# ATmega128RFA1-DevBoard.net
KiCad netlist of a schematic drawn in EAGLE
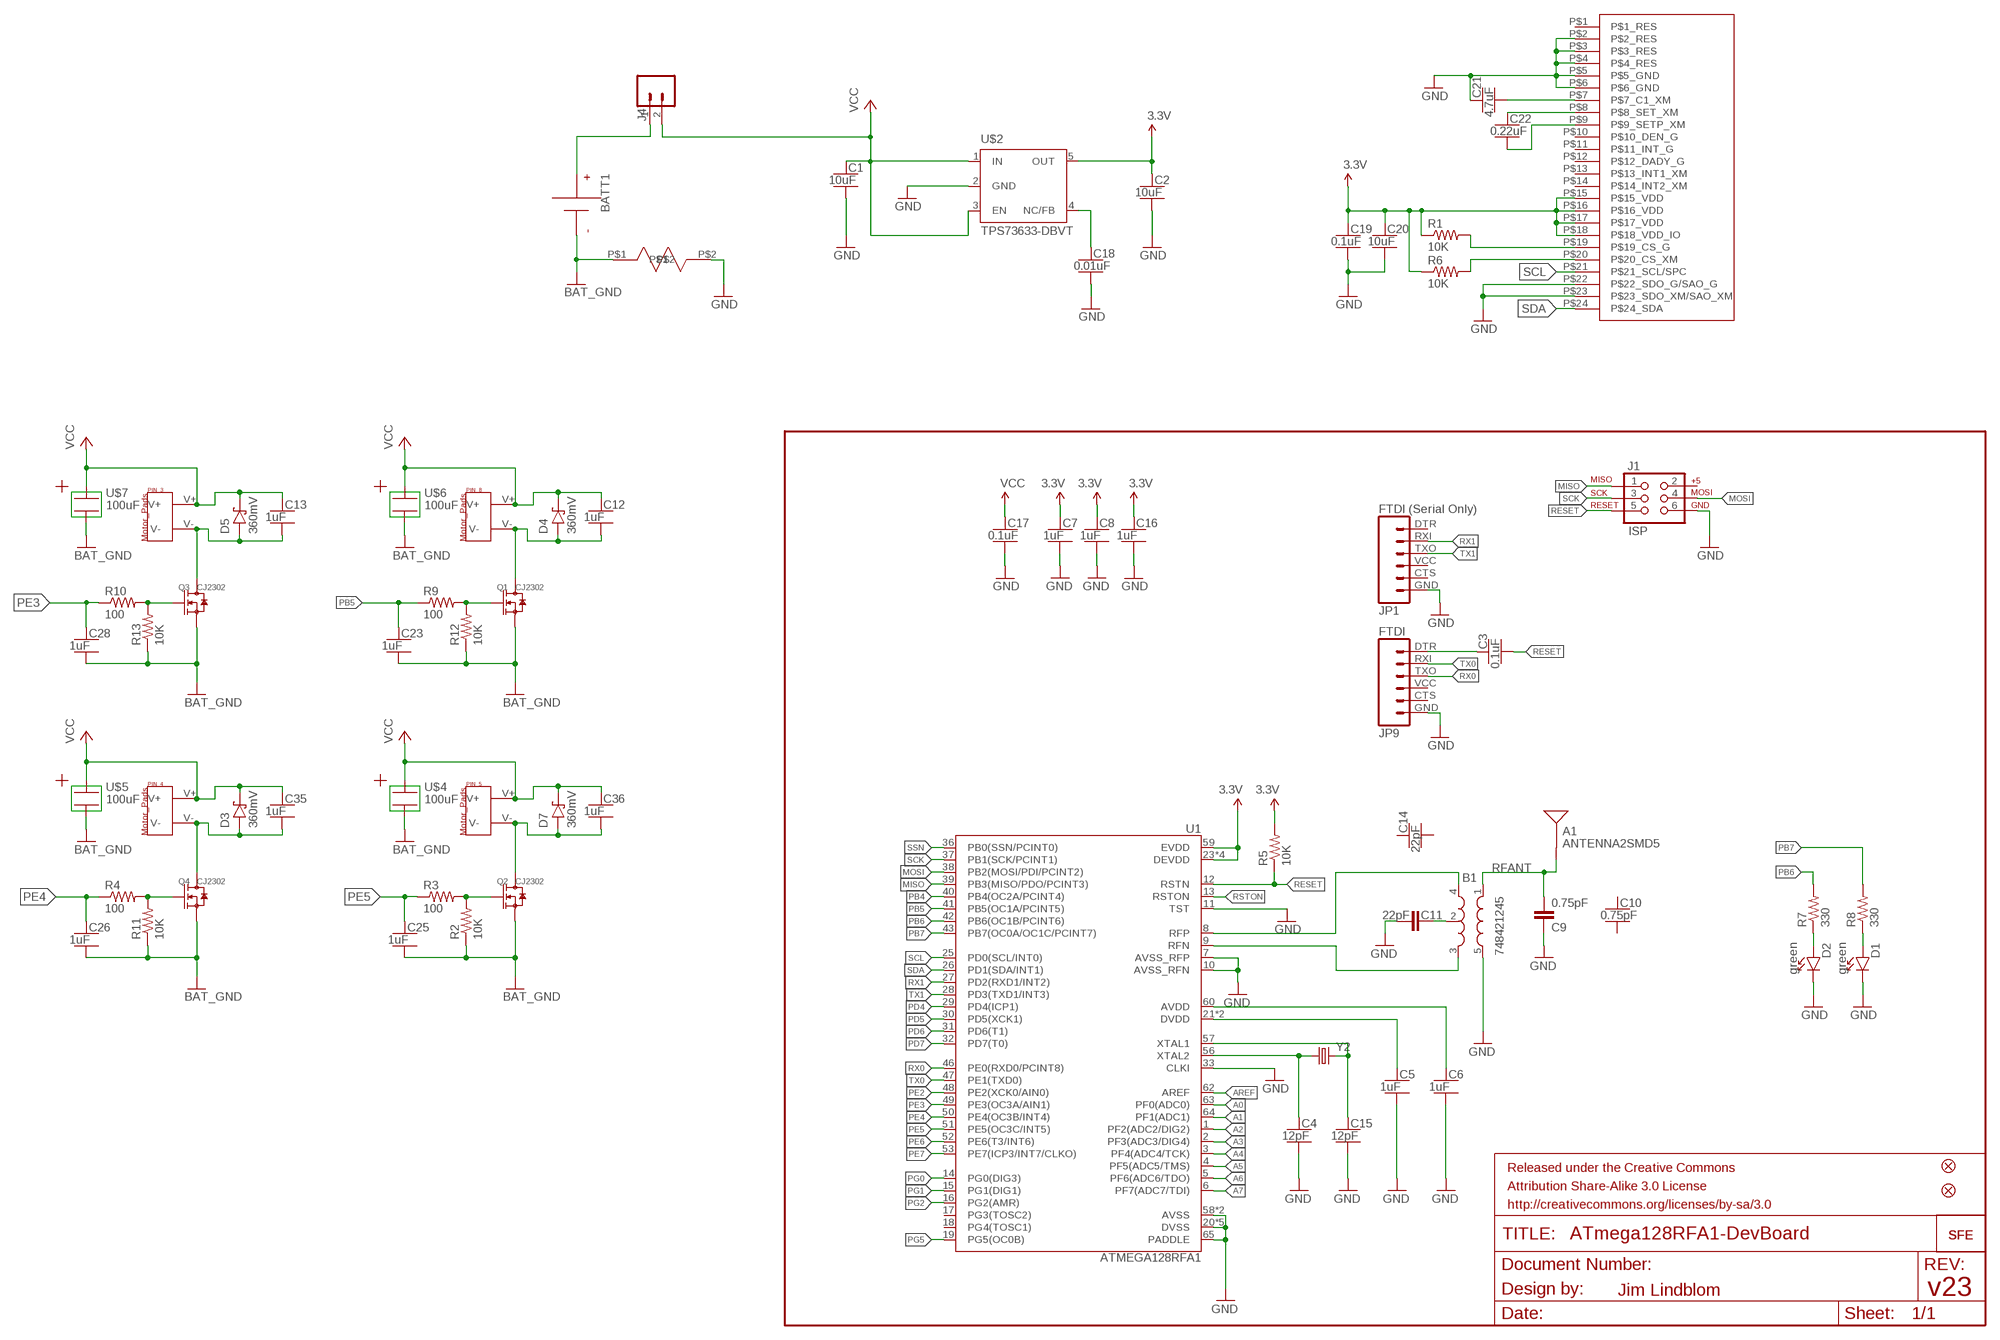
[diagram p0: schematic, sheet 1]

(export (version "E")
  (design (tool "Eeschema 10.0.6"))
  (components
    (comp (ref "A1")
      (value "ANTENNA2SMD5")
      (footprint "eagle-import:ANTENNA-CHIP5")
      (libsource (lib "eagle-import") (part "ANTENNA2SMD5"))
    )
    (comp (ref "B1")
      (value "748421245")
      (footprint "eagle-import:BALUN")
      (libsource (lib "eagle-import") (part "BALUN0805"))
    )
    (comp (ref "BATT1")
      (value "BATTERY-HUBSAN-W/HOLDER")
      (footprint "eagle-import:BATTERY-W_HOLDER-380MAH-HUBSAN")
      (libsource (lib "eagle-import") (part "BATTERY-HUBSAN-W/HOLDER"))
    )
    (comp (ref "C1")
      (value "10uF")
      (footprint "eagle-import:CAPC2012X140_HS")
      (fields
        (field (name "MFR") "Murata Electronics North America")
        (field (name "MPN") "GRM21BR61E106KA73L")
      )
      (libsource (lib "eagle-import") (part "CAPACITOR-NP_SMD-2012-0805_CERAMIC-10UF"))
    )
    (comp (ref "C2")
      (value "10uF")
      (footprint "eagle-import:CAPC2012X140_HS")
      (fields
        (field (name "MFR") "Murata Electronics North America")
        (field (name "MPN") "GRM21BR61E106KA73L")
      )
      (libsource (lib "eagle-import") (part "CAPACITOR-NP_SMD-2012-0805_CERAMIC-10UF"))
    )
    (comp (ref "C3")
      (value "0.1uF")
      (footprint "eagle-import:CAPC2012X140_HS")
      (fields
        (field (name "MFR") "Murata Electronics North America")
        (field (name "MPN") "GRM21BR71H104KA01L")
      )
      (libsource (lib "eagle-import") (part "CAPACITOR-NP_SMD-2012-0805_CERAMIC-0.1UF"))
    )
    (comp (ref "C4")
      (value "12pF")
      (footprint "eagle-import:CAPC2012X140_HS")
      (fields
        (field (name "MFR") "Murata Electronics North America")
        (field (name "MPN") "GRM21A5C2E120JW01D")
      )
      (libsource (lib "eagle-import") (part "CAPACITOR-NP_SMD-2012-0805_CERAMIC-12PF"))
    )
    (comp (ref "C5")
      (value "1uF")
      (footprint "eagle-import:CAPC2012X140_HS")
      (fields
        (field (name "MFR") "Murata Electronics North America")
        (field (name "MPN") "GRM21BR71H105KA12L")
      )
      (libsource (lib "eagle-import") (part "CAPACITOR-NP_SMD-2012-0805_CERAMIC-1UF"))
    )
    (comp (ref "C6")
      (value "1uF")
      (footprint "eagle-import:CAPC2012X140_HS")
      (fields
        (field (name "MFR") "Murata Electronics North America")
        (field (name "MPN") "GRM21BR71H105KA12L")
      )
      (libsource (lib "eagle-import") (part "CAPACITOR-NP_SMD-2012-0805_CERAMIC-1UF"))
    )
    (comp (ref "C7")
      (value "1uF")
      (footprint "eagle-import:CAPC2012X140_HS")
      (fields
        (field (name "MFR") "Murata Electronics North America")
        (field (name "MPN") "GRM21BR71H105KA12L")
      )
      (libsource (lib "eagle-import") (part "CAPACITOR-NP_SMD-2012-0805_CERAMIC-1UF"))
    )
    (comp (ref "C8")
      (value "1uF")
      (footprint "eagle-import:CAPC2012X140_HS")
      (fields
        (field (name "MFR") "Murata Electronics North America")
        (field (name "MPN") "GRM21BR71H105KA12L")
      )
      (libsource (lib "eagle-import") (part "CAPACITOR-NP_SMD-2012-0805_CERAMIC-1UF"))
    )
    (comp (ref "C9")
      (value "0.75pF")
      (footprint "eagle-import:0402-CAP")
      (libsource (lib "eagle-import") (part "CAP0402-CAP"))
    )
    (comp (ref "C10")
      (value "0.75pF")
      (footprint "eagle-import:CAPC2012X140_HS")
      (fields
        (field (name "MFR") "Murata Electronics North America")
        (field (name "MPN") "GQM2195C2AR75CB01D")
      )
      (libsource (lib "eagle-import") (part "CAPACITOR-NP_SMD-2012-0805_CERAMIC-0.75PF"))
    )
    (comp (ref "C11")
      (value "22pF")
      (footprint "eagle-import:0402-CAP")
      (libsource (lib "eagle-import") (part "CAP0402-CAP"))
    )
    (comp (ref "C12")
      (value "1uF")
      (footprint "eagle-import:CAPC2012X140_HS")
      (fields
        (field (name "MFR") "Murata Electronics North America")
        (field (name "MPN") "GRM21BR71H105KA12L")
      )
      (libsource (lib "eagle-import") (part "CAPACITOR-NP_SMD-2012-0805_CERAMIC-1UF"))
    )
    (comp (ref "C13")
      (value "1uF")
      (footprint "eagle-import:CAPC2012X140_HS")
      (fields
        (field (name "MFR") "Murata Electronics North America")
        (field (name "MPN") "GRM21BR71H105KA12L")
      )
      (libsource (lib "eagle-import") (part "CAPACITOR-NP_SMD-2012-0805_CERAMIC-1UF"))
    )
    (comp (ref "C14")
      (value "22pF")
      (footprint "eagle-import:CAPC2012X140_HS")
      (fields
        (field (name "MFR") "Murata Electronics North America")
        (field (name "MPN") "GRM21A5C2E220JW01D")
      )
      (libsource (lib "eagle-import") (part "CAPACITOR-NP_SMD-2012-0805_CERAMIC-22PF"))
    )
    (comp (ref "C15")
      (value "12pF")
      (footprint "eagle-import:CAPC2012X140_HS")
      (fields
        (field (name "MFR") "Murata Electronics North America")
        (field (name "MPN") "GRM21A5C2E120JW01D")
      )
      (libsource (lib "eagle-import") (part "CAPACITOR-NP_SMD-2012-0805_CERAMIC-12PF"))
    )
    (comp (ref "C16")
      (value "1uF")
      (footprint "eagle-import:CAPC2012X140_HS")
      (fields
        (field (name "MFR") "Murata Electronics North America")
        (field (name "MPN") "GRM21BR71H105KA12L")
      )
      (libsource (lib "eagle-import") (part "CAPACITOR-NP_SMD-2012-0805_CERAMIC-1UF"))
    )
    (comp (ref "C17")
      (value "0.1uF")
      (footprint "eagle-import:CAPC2012X140_HS")
      (fields
        (field (name "MFR") "Murata Electronics North America")
        (field (name "MPN") "GRM21BR71H104KA01L")
      )
      (libsource (lib "eagle-import") (part "CAPACITOR-NP_SMD-2012-0805_CERAMIC-0.1UF"))
    )
    (comp (ref "C18")
      (value "0.01uF")
      (footprint "eagle-import:CAPC2012X140_HS")
      (fields
        (field (name "MFR") "Murata Electronics North America")
        (field (name "MPN") "GRM2195C1H103FA01D")
      )
      (libsource (lib "eagle-import") (part "CAPACITOR-NP_SMD-2012-0805_CERAMIC-0.01UF"))
    )
    (comp (ref "C19")
      (value "0.1uF")
      (footprint "eagle-import:CAPC2012X140_HS")
      (fields
        (field (name "MFR") "Murata Electronics North America")
        (field (name "MPN") "GRM21BR71H104KA01L")
      )
      (libsource (lib "eagle-import") (part "CAPACITOR-NP_SMD-2012-0805_CERAMIC-0.1UF"))
    )
    (comp (ref "C20")
      (value "10uF")
      (footprint "eagle-import:CAPC2012X140_HS")
      (fields
        (field (name "MFR") "Murata Electronics North America")
        (field (name "MPN") "GRM21BR61E106KA73L")
      )
      (libsource (lib "eagle-import") (part "CAPACITOR-NP_SMD-2012-0805_CERAMIC-10UF"))
    )
    (comp (ref "C21")
      (value "4.7uF")
      (footprint "eagle-import:CAPC2012X140_HS")
      (fields
        (field (name "MFR") "Murata Electronics North America")
        (field (name "MPN") "GRM21BR61E475KA12L")
      )
      (libsource (lib "eagle-import") (part "CAPACITOR-NP_SMD-2012-0805_CERAMIC-4.7UF"))
    )
    (comp (ref "C22")
      (value "0.22uF")
      (footprint "eagle-import:CAPC2012X140_HS")
      (fields
        (field (name "MFR") "Murata Electronics North America")
        (field (name "MPN") "GRM21BR71H224KA01L")
      )
      (libsource (lib "eagle-import") (part "CAPACITOR-NP_SMD-2012-0805_CERAMIC-0.22UF"))
    )
    (comp (ref "C23")
      (value "1uF")
      (footprint "eagle-import:CAPC2012X140_HS")
      (fields
        (field (name "MFR") "Murata Electronics North America")
        (field (name "MPN") "GRM21BR71H105KA12L")
      )
      (libsource (lib "eagle-import") (part "CAPACITOR-NP_SMD-2012-0805_CERAMIC-1UF"))
    )
    (comp (ref "C25")
      (value "1uF")
      (footprint "eagle-import:CAPC2012X140_HS")
      (fields
        (field (name "MFR") "Murata Electronics North America")
        (field (name "MPN") "GRM21BR71H105KA12L")
      )
      (libsource (lib "eagle-import") (part "CAPACITOR-NP_SMD-2012-0805_CERAMIC-1UF"))
    )
    (comp (ref "C26")
      (value "1uF")
      (footprint "eagle-import:CAPC2012X140_HS")
      (fields
        (field (name "MFR") "Murata Electronics North America")
        (field (name "MPN") "GRM21BR71H105KA12L")
      )
      (libsource (lib "eagle-import") (part "CAPACITOR-NP_SMD-2012-0805_CERAMIC-1UF"))
    )
    (comp (ref "C28")
      (value "1uF")
      (footprint "eagle-import:CAPC2012X140_HS")
      (fields
        (field (name "MFR") "Murata Electronics North America")
        (field (name "MPN") "GRM21BR71H105KA12L")
      )
      (libsource (lib "eagle-import") (part "CAPACITOR-NP_SMD-2012-0805_CERAMIC-1UF"))
    )
    (comp (ref "C35")
      (value "1uF")
      (footprint "eagle-import:CAPC2012X140_HS")
      (fields
        (field (name "MFR") "Murata Electronics North America")
        (field (name "MPN") "GRM21BR71H105KA12L")
      )
      (libsource (lib "eagle-import") (part "CAPACITOR-NP_SMD-2012-0805_CERAMIC-1UF"))
    )
    (comp (ref "C36")
      (value "1uF")
      (footprint "eagle-import:CAPC2012X140_HS")
      (fields
        (field (name "MFR") "Murata Electronics North America")
        (field (name "MPN") "GRM21BR71H105KA12L")
      )
      (libsource (lib "eagle-import") (part "CAPACITOR-NP_SMD-2012-0805_CERAMIC-1UF"))
    )
    (comp (ref "D1")
      (value "green")
      (footprint "eagle-import:LEDSC125X200X120-2_HS")
      (fields (field (name "MFR") "Lite-On Inc") (field (name "MPN") "LTST-C170GKT"))
      (libsource (lib "eagle-import") (part "DIODE-LED_SMD-2012-0805-GREEN"))
    )
    (comp (ref "D2")
      (value "green")
      (footprint "eagle-import:LEDSC125X200X120-2_HS")
      (fields (field (name "MFR") "Lite-On Inc") (field (name "MPN") "LTST-C170GKT"))
      (libsource (lib "eagle-import") (part "DIODE-LED_SMD-2012-0805-GREEN"))
    )
    (comp (ref "D3")
      (value "360mV")
      (footprint "eagle-import:SOD3716X135_HS")
      (fields
        (field (name "MFR") "Toshiba Semiconductor and Storage")
        (field (name "MPN") "CRS08(TE85L,Q,M)")
      )
      (libsource (lib "eagle-import") (part "DIODE-SCHOTTKY_SMD-SOD123-360MV"))
    )
    (comp (ref "D4")
      (value "360mV")
      (footprint "eagle-import:SOD3716X135_HS")
      (fields
        (field (name "MFR") "Toshiba Semiconductor and Storage")
        (field (name "MPN") "CRS08(TE85L,Q,M)")
      )
      (libsource (lib "eagle-import") (part "DIODE-SCHOTTKY_SMD-SOD123-360MV"))
    )
    (comp (ref "D5")
      (value "360mV")
      (footprint "eagle-import:SOD3716X135_HS")
      (fields
        (field (name "MFR") "Toshiba Semiconductor and Storage")
        (field (name "MPN") "CRS08(TE85L,Q,M)")
      )
      (libsource (lib "eagle-import") (part "DIODE-SCHOTTKY_SMD-SOD123-360MV"))
    )
    (comp (ref "D7")
      (value "360mV")
      (footprint "eagle-import:SOD3716X135_HS")
      (fields
        (field (name "MFR") "Toshiba Semiconductor and Storage")
        (field (name "MPN") "CRS08(TE85L,Q,M)")
      )
      (libsource (lib "eagle-import") (part "DIODE-SCHOTTKY_SMD-SOD123-360MV"))
    )
    (comp (ref "FID1")
      (value "FIDUCIALUFIDUCIAL")
      (footprint "eagle-import:MICRO-FIDUCIAL")
      (libsource (lib "eagle-import") (part "FIDUCIALUFIDUCIAL"))
    )
    (comp (ref "FID2")
      (value "FIDUCIALUFIDUCIAL")
      (footprint "eagle-import:MICRO-FIDUCIAL")
      (libsource (lib "eagle-import") (part "FIDUCIALUFIDUCIAL"))
    )
    (comp (ref "J1")
      (value "ISP")
      (footprint "eagle-import:2X3-NS")
      (libsource (lib "eagle-import") (part "AVR_SPI_PRG_6NS"))
    )
    (comp (ref "J4")
      (value "MALE_HEADER_2POS-2X1-0.1IN")
      (footprint "eagle-import:MALE_HEADER_2X1_0.1IN")
      (fields
        (field (name "MFR") "3M")
        (field (name "MPN") "961102-6404-AR")
        (field (name "CREATOR") "SWANSON")
      )
      (libsource (lib "eagle-import") (part "MALE_HEADER_2POS-2X1-0.1IN"))
    )
    (comp (ref "JP1")
      (value "FTDI (Serial Only)")
      (footprint "eagle-import:FTDI_BASIC")
      (libsource (lib "eagle-import") (part "FTDI_BASICPTH"))
    )
    (comp (ref "JP4")
      (value "LOGO-SFENEW")
      (footprint "eagle-import:SFE-NEW-WEBLOGO")
      (libsource (lib "eagle-import") (part "LOGO-SFENEW"))
    )
    (comp (ref "JP9")
      (value "FTDI")
      (footprint "eagle-import:FTDI_BASIC")
      (libsource (lib "eagle-import") (part "FTDI_BASICPTH"))
    )
    (comp (ref "JP10")
      (value "LOGO-SFENEW")
      (footprint "eagle-import:SFE-NEW-WEBLOGO")
      (libsource (lib "eagle-import") (part "LOGO-SFENEW"))
    )
    (comp (ref "PIN_3")
      (value "MOTOR_PADS")
      (footprint "eagle-import:MOTOR_PADS")
      (libsource (lib "eagle-import") (part "MOTOR_PADS"))
    )
    (comp (ref "PIN_4")
      (value "MOTOR_PADS")
      (footprint "eagle-import:MOTOR_PADS")
      (libsource (lib "eagle-import") (part "MOTOR_PADS"))
    )
    (comp (ref "PIN_5")
      (value "MOTOR_PADS")
      (footprint "eagle-import:MOTOR_PADS")
      (libsource (lib "eagle-import") (part "MOTOR_PADS"))
    )
    (comp (ref "PIN_8")
      (value "MOTOR_PADS")
      (footprint "eagle-import:MOTOR_PADS")
      (libsource (lib "eagle-import") (part "MOTOR_PADS"))
    )
    (comp (ref "Q1")
      (value "CJ2302")
      (footprint "eagle-import:SOT-23")
      (libsource (lib "eagle-import") (part "SMD-MOSFET-N-CH-20V-2.1A-CJ2302(SOT-23)"))
    )
    (comp (ref "Q2")
      (value "CJ2302")
      (footprint "eagle-import:SOT-23")
      (libsource (lib "eagle-import") (part "SMD-MOSFET-N-CH-20V-2.1A-CJ2302(SOT-23)"))
    )
    (comp (ref "Q3")
      (value "CJ2302")
      (footprint "eagle-import:SOT-23")
      (libsource (lib "eagle-import") (part "SMD-MOSFET-N-CH-20V-2.1A-CJ2302(SOT-23)"))
    )
    (comp (ref "Q4")
      (value "CJ2302")
      (footprint "eagle-import:SOT-23")
      (libsource (lib "eagle-import") (part "SMD-MOSFET-N-CH-20V-2.1A-CJ2302(SOT-23)"))
    )
    (comp (ref "R1")
      (value "10K")
      (footprint "eagle-import:RESC2012X60_HS")
      (fields (field (name "MFR") "Yageo") (field (name "MPN") "RC0805JR-0710KL"))
      (libsource (lib "eagle-import") (part "RESISTOR_SMD-2012-0805-10K"))
    )
    (comp (ref "R2")
      (value "10K")
      (footprint "eagle-import:RESC2012X60_HS")
      (fields (field (name "MFR") "Yageo") (field (name "MPN") "RC0805JR-0710KL"))
      (libsource (lib "eagle-import") (part "RESISTOR_SMD-2012-0805-10K"))
    )
    (comp (ref "R3")
      (value "100")
      (footprint "eagle-import:RESC2012X60_HS")
      (fields (field (name "MFR") "Yageo") (field (name "MPN") "RC0805JR-07100RL"))
      (libsource (lib "eagle-import") (part "RESISTOR_SMD-2012-0805-100"))
    )
    (comp (ref "R4")
      (value "100")
      (footprint "eagle-import:RESC2012X60_HS")
      (fields (field (name "MFR") "Yageo") (field (name "MPN") "RC0805JR-07100RL"))
      (libsource (lib "eagle-import") (part "RESISTOR_SMD-2012-0805-100"))
    )
    (comp (ref "R5")
      (value "10K")
      (footprint "eagle-import:RESC2012X60_HS")
      (fields (field (name "MFR") "Yageo") (field (name "MPN") "RC0805JR-0710KL"))
      (libsource (lib "eagle-import") (part "RESISTOR_SMD-2012-0805-10K"))
    )
    (comp (ref "R6")
      (value "10K")
      (footprint "eagle-import:RESC2012X60_HS")
      (fields (field (name "MFR") "Yageo") (field (name "MPN") "RC0805JR-0710KL"))
      (libsource (lib "eagle-import") (part "RESISTOR_SMD-2012-0805-10K"))
    )
    (comp (ref "R7")
      (value "330")
      (footprint "eagle-import:RESC2012X60_HS")
      (fields (field (name "MFR") "Yageo") (field (name "MPN") "RC0805JR-07330RL"))
      (libsource (lib "eagle-import") (part "RESISTOR_SMD-2012-0805-330"))
    )
    (comp (ref "R8")
      (value "330")
      (footprint "eagle-import:RESC2012X60_HS")
      (fields (field (name "MFR") "Yageo") (field (name "MPN") "RC0805JR-07330RL"))
      (libsource (lib "eagle-import") (part "RESISTOR_SMD-2012-0805-330"))
    )
    (comp (ref "R9")
      (value "100")
      (footprint "eagle-import:RESC2012X60_HS")
      (fields (field (name "MFR") "Yageo") (field (name "MPN") "RC0805JR-07100RL"))
      (libsource (lib "eagle-import") (part "RESISTOR_SMD-2012-0805-100"))
    )
    (comp (ref "R10")
      (value "100")
      (footprint "eagle-import:RESC2012X60_HS")
      (fields (field (name "MFR") "Yageo") (field (name "MPN") "RC0805JR-07100RL"))
      (libsource (lib "eagle-import") (part "RESISTOR_SMD-2012-0805-100"))
    )
    (comp (ref "R11")
      (value "10K")
      (footprint "eagle-import:RESC2012X60_HS")
      (fields (field (name "MFR") "Yageo") (field (name "MPN") "RC0805JR-0710KL"))
      (libsource (lib "eagle-import") (part "RESISTOR_SMD-2012-0805-10K"))
    )
    (comp (ref "R12")
      (value "10K")
      (footprint "eagle-import:RESC2012X60_HS")
      (fields (field (name "MFR") "Yageo") (field (name "MPN") "RC0805JR-0710KL"))
      (libsource (lib "eagle-import") (part "RESISTOR_SMD-2012-0805-10K"))
    )
    (comp (ref "R13")
      (value "10K")
      (footprint "eagle-import:RESC2012X60_HS")
      (fields (field (name "MFR") "Yageo") (field (name "MPN") "RC0805JR-0710KL"))
      (libsource (lib "eagle-import") (part "RESISTOR_SMD-2012-0805-10K"))
    )
    (comp (ref "U$1")
      (value "IMU")
      (footprint "eagle-import:LGA-24_4X4MM")
      (fields (field (name "MFR") "STMicroelectronics"))
      (libsource (lib "eagle-import") (part "IMU"))
    )
    (comp (ref "U$2")
      (value "TPS73633-DBVT")
      (footprint "eagle-import:SOT23-DBV")
      (fields (field (name "MFR") "Texas Instruments") (field (name "MPN") "LP3985IM5X-3.0/NOPB"))
      (libsource (lib "eagle-import") (part "TPS73633-DBVT"))
    )
    (comp (ref "U$3")
      (value "0")
      (footprint "eagle-import:SMD_RESISTOR")
      (fields (field (name "MFR") "Yageo") (field (name "MPN") "RC0805JR-070RL"))
      (libsource (lib "eagle-import") (part "RESISTOR"))
    )
    (comp (ref "U$4")
      (value "100uF")
      (footprint "eagle-import:TAJB_SMB_POLAR_CAP")
      (fields (field (name "MFR") "AVX Corporation") (field (name "MPN") "TAJB107K006RNJ"))
      (libsource (lib "eagle-import") (part "POLAR_CAP"))
    )
    (comp (ref "U$5")
      (value "100uF")
      (footprint "eagle-import:TAJB_SMB_POLAR_CAP")
      (fields (field (name "MFR") "AVX Corporation") (field (name "MPN") "TAJB107K006RNJ"))
      (libsource (lib "eagle-import") (part "POLAR_CAP"))
    )
    (comp (ref "U$6")
      (value "100uF")
      (footprint "eagle-import:TAJB_SMB_POLAR_CAP")
      (fields (field (name "MFR") "AVX Corporation") (field (name "MPN") "TAJB107K006RNJ"))
      (libsource (lib "eagle-import") (part "POLAR_CAP"))
    )
    (comp (ref "U$7")
      (value "100uF")
      (footprint "eagle-import:TAJB_SMB_POLAR_CAP")
      (fields (field (name "MFR") "AVX Corporation") (field (name "MPN") "TAJB107K006RNJ"))
      (libsource (lib "eagle-import") (part "POLAR_CAP"))
    )
    (comp (ref "U1")
      (value "ATMEGA128RFA1")
      (footprint "eagle-import:QFN-64")
      (libsource (lib "eagle-import") (part "ATMEGA128RFA1"))
    )
    (comp (ref "Y2")
      (value "CRYSTAL5X3")
      (footprint "eagle-import:CRYSTAL-SMD-5X3")
      (fields (field (name "MFR") "Abracon LLC") (field (name "MPN") "ABM3B-16.000MHZ-B2-T"))
      (libsource (lib "eagle-import") (part "CRYSTAL5X3"))
    )
  )
  (nets
    (net (code "1") (name "/RFANT") (class "Default")
      (node (ref "A1") (pin "FEED") (pinfunction "SIGNAL_FEED") (pintype "bidirectional"))
      (node (ref "B1") (pin "1") (pinfunction "IN_1") (pintype "bidirectional"))
      (node (ref "C9") (pin "2") (pinfunction "2_2") (pintype "passive"))
    )
    (net (code "2") (name "3.3V") (class "Default")
      (node (ref "C16") (pin "1") (pinfunction "1_1") (pintype "passive"))
      (node (ref "C19") (pin "1") (pinfunction "1_1") (pintype "passive"))
      (node (ref "C2") (pin "1") (pinfunction "1_1") (pintype "passive"))
      (node (ref "C20") (pin "1") (pinfunction "1_1") (pintype "passive"))
      (node (ref "C7") (pin "1") (pinfunction "1_1") (pintype "passive"))
      (node (ref "C8") (pin "1") (pinfunction "1_1") (pintype "passive"))
      (node (ref "R1") (pin "1") (pinfunction "1_1") (pintype "passive"))
      (node (ref "R5") (pin "2") (pinfunction "2_2") (pintype "passive"))
      (node (ref "R6") (pin "1") (pinfunction "1_1") (pintype "passive"))
      (node (ref "U$1") (pin "P$15") (pinfunction "P$15_VDD_P$15") (pintype "bidirectional"))
      (node (ref "U$1") (pin "P$16") (pinfunction "P$16_VDD_P$16") (pintype "bidirectional"))
      (node (ref "U$1") (pin "P$17") (pinfunction "P$17_VDD_P$17") (pintype "bidirectional"))
      (node (ref "U$1") (pin "P$18") (pinfunction "P$18_VDD_IO_P$18") (pintype "bidirectional"))
      (node (ref "U$2") (pin "5") (pinfunction "OUT_5") (pintype "passive"))
      (node (ref "U1") (pin "23") (pinfunction "DEVDD_23") (pintype "bidirectional"))
      (node (ref "U1") (pin "34") (pinfunction "DEVDD_34") (pintype "bidirectional"))
      (node (ref "U1") (pin "44") (pinfunction "DEVDD_44") (pintype "bidirectional"))
      (node (ref "U1") (pin "54") (pinfunction "DEVDD_54") (pintype "bidirectional"))
      (node (ref "U1") (pin "59") (pinfunction "EVDD_59") (pintype "bidirectional"))
    )
    (net (code "3") (name "A0") (class "Default")
      (node (ref "U1") (pin "63") (pinfunction "PF0(ADC0)_63") (pintype "bidirectional"))
    )
    (net (code "4") (name "A1") (class "Default")
      (node (ref "U1") (pin "64") (pinfunction "PF1(ADC1)_64") (pintype "bidirectional"))
    )
    (net (code "5") (name "A2") (class "Default")
      (node (ref "U1") (pin "1") (pinfunction "PF2(ADC2/DIG2)_1") (pintype "bidirectional"))
    )
    (net (code "6") (name "A3") (class "Default")
      (node (ref "U1") (pin "2") (pinfunction "PF3(ADC3/DIG4)_2") (pintype "bidirectional"))
    )
    (net (code "7") (name "A4") (class "Default")
      (node (ref "U1") (pin "3") (pinfunction "PF4(ADC4/TCK)_3") (pintype "bidirectional"))
    )
    (net (code "8") (name "A5") (class "Default")
      (node (ref "U1") (pin "4") (pinfunction "PF5(ADC5/TMS)_4") (pintype "bidirectional"))
    )
    (net (code "9") (name "A6") (class "Default")
      (node (ref "U1") (pin "5") (pinfunction "PF6(ADC6/TDO)_5") (pintype "bidirectional"))
    )
    (net (code "10") (name "A7") (class "Default")
      (node (ref "U1") (pin "6") (pinfunction "PF7(ADC7/TDI)_6") (pintype "bidirectional"))
    )
    (net (code "11") (name "AREF") (class "Default")
      (node (ref "U1") (pin "62") (pinfunction "AREF_62") (pintype "bidirectional"))
    )
    (net (code "12") (name "BAT_GND") (class "Default")
      (node (ref "BATT1") (pin "-") (pinfunction "N_-") (pintype "bidirectional"))
      (node (ref "C23") (pin "2") (pinfunction "2_2") (pintype "passive"))
      (node (ref "C25") (pin "2") (pinfunction "2_2") (pintype "passive"))
      (node (ref "C26") (pin "2") (pinfunction "2_2") (pintype "passive"))
      (node (ref "C28") (pin "2") (pinfunction "2_2") (pintype "passive"))
      (node (ref "Q1") (pin "2") (pinfunction "S_2") (pintype "passive"))
      (node (ref "Q2") (pin "2") (pinfunction "S_2") (pintype "passive"))
      (node (ref "Q3") (pin "2") (pinfunction "S_2") (pintype "passive"))
      (node (ref "Q4") (pin "2") (pinfunction "S_2") (pintype "passive"))
      (node (ref "R11") (pin "1") (pinfunction "1_1") (pintype "passive"))
      (node (ref "R12") (pin "1") (pinfunction "1_1") (pintype "passive"))
      (node (ref "R13") (pin "1") (pinfunction "1_1") (pintype "passive"))
      (node (ref "R2") (pin "1") (pinfunction "1_1") (pintype "passive"))
      (node (ref "U$3") (pin "P$1") (pinfunction "P$1_P$1") (pintype "bidirectional"))
      (node (ref "U$4") (pin "P$2") (pinfunction "2_P$2") (pintype "passive"))
      (node (ref "U$5") (pin "P$2") (pinfunction "2_P$2") (pintype "passive"))
      (node (ref "U$6") (pin "P$2") (pinfunction "2_P$2") (pintype "passive"))
      (node (ref "U$7") (pin "P$2") (pinfunction "2_P$2") (pintype "passive"))
    )
    (net (code "13") (name "GND") (class "Default")
      (node (ref "B1") (pin "5") (pinfunction "GND_5") (pintype "bidirectional"))
      (node (ref "C1") (pin "2") (pinfunction "2_2") (pintype "passive"))
      (node (ref "C11") (pin "2") (pinfunction "2_2") (pintype "passive"))
      (node (ref "C15") (pin "2") (pinfunction "2_2") (pintype "passive"))
      (node (ref "C16") (pin "2") (pinfunction "2_2") (pintype "passive"))
      (node (ref "C17") (pin "2") (pinfunction "2_2") (pintype "passive"))
      (node (ref "C18") (pin "2") (pinfunction "2_2") (pintype "passive"))
      (node (ref "C19") (pin "2") (pinfunction "2_2") (pintype "passive"))
      (node (ref "C2") (pin "2") (pinfunction "2_2") (pintype "passive"))
      (node (ref "C20") (pin "2") (pinfunction "2_2") (pintype "passive"))
      (node (ref "C21") (pin "1") (pinfunction "1_1") (pintype "passive"))
      (node (ref "C4") (pin "2") (pinfunction "2_2") (pintype "passive"))
      (node (ref "C5") (pin "2") (pinfunction "2_2") (pintype "passive"))
      (node (ref "C6") (pin "2") (pinfunction "2_2") (pintype "passive"))
      (node (ref "C7") (pin "2") (pinfunction "2_2") (pintype "passive"))
      (node (ref "C8") (pin "2") (pinfunction "2_2") (pintype "passive"))
      (node (ref "C9") (pin "1") (pinfunction "1_1") (pintype "passive"))
      (node (ref "D1") (pin "C") (pinfunction "C_C") (pintype "passive"))
      (node (ref "D2") (pin "C") (pinfunction "C_C") (pintype "passive"))
      (node (ref "J1") (pin "6") (pinfunction "6_6") (pintype "passive"))
      (node (ref "JP1") (pin "GND") (pinfunction "6_GND") (pintype "passive"))
      (node (ref "JP9") (pin "GND") (pinfunction "6_GND") (pintype "passive"))
      (node (ref "U$1") (pin "P$2") (pinfunction "P$2_RES_P$2") (pintype "bidirectional"))
      (node (ref "U$1") (pin "P$22") (pinfunction "P$22_SDO_G/SAO_G_P$22") (pintype "bidirectional"))
      (node (ref "U$1") (pin "P$23") (pinfunction "P$23_SDO_XM/SAO_XM_P$23") (pintype "bidirectional"))
      (node (ref "U$1") (pin "P$3") (pinfunction "P$3_RES_P$3") (pintype "bidirectional"))
      (node (ref "U$1") (pin "P$4") (pinfunction "P$4_RES_P$4") (pintype "bidirectional"))
      (node (ref "U$1") (pin "P$5") (pinfunction "P$5_GND_P$5") (pintype "bidirectional"))
      (node (ref "U$1") (pin "P$6") (pinfunction "P$6_GND_P$6") (pintype "bidirectional"))
      (node (ref "U$2") (pin "2") (pinfunction "GND_2") (pintype "input"))
      (node (ref "U$3") (pin "P$2") (pinfunction "P$2_P$2") (pintype "bidirectional"))
      (node (ref "U1") (pin "10") (pinfunction "AVSS_RFN_10") (pintype "bidirectional"))
      (node (ref "U1") (pin "11") (pinfunction "TST_11") (pintype "bidirectional"))
      (node (ref "U1") (pin "20") (pinfunction "DVSS_20") (pintype "bidirectional"))
      (node (ref "U1") (pin "24") (pinfunction "DVSS_24") (pintype "bidirectional"))
      (node (ref "U1") (pin "33") (pinfunction "CLKI_33") (pintype "bidirectional"))
      (node (ref "U1") (pin "35") (pinfunction "DVSS_35") (pintype "bidirectional"))
      (node (ref "U1") (pin "45") (pinfunction "DVSS_45") (pintype "bidirectional"))
      (node (ref "U1") (pin "55") (pinfunction "DVSS_55") (pintype "bidirectional"))
      (node (ref "U1") (pin "58") (pinfunction "AVSS_58") (pintype "bidirectional"))
      (node (ref "U1") (pin "61") (pinfunction "AVSS_61") (pintype "bidirectional"))
      (node (ref "U1") (pin "65") (pinfunction "PADDLE_65") (pintype "bidirectional"))
      (node (ref "U1") (pin "7") (pinfunction "AVSS_RFP_7") (pintype "bidirectional"))
    )
    (net (code "14") (name "MISO") (class "Default")
      (node (ref "J1") (pin "1") (pinfunction "1_1") (pintype "passive"))
      (node (ref "U1") (pin "39") (pinfunction "PB3(MISO/PDO/PCINT3)_39") (pintype "bidirectional"))
    )
    (net (code "15") (name "MOSI") (class "Default")
      (node (ref "J1") (pin "4") (pinfunction "4_4") (pintype "passive"))
      (node (ref "U1") (pin "38") (pinfunction "PB2(MOSI/PDI/PCINT2)_38") (pintype "bidirectional"))
    )
    (net (code "16") (name "Net-(B1-GND-Pad2)") (class "Default")
      (node (ref "B1") (pin "2") (pinfunction "GND_2") (pintype "bidirectional"))
      (node (ref "C11") (pin "1") (pinfunction "1_1") (pintype "passive"))
    )
    (net (code "17") (name "Net-(B1-OUT1)") (class "Default")
      (node (ref "B1") (pin "4") (pinfunction "OUT1_4") (pintype "bidirectional"))
      (node (ref "U1") (pin "8") (pinfunction "RFP_8") (pintype "bidirectional"))
    )
    (net (code "18") (name "Net-(B1-OUT2)") (class "Default")
      (node (ref "B1") (pin "3") (pinfunction "OUT2_3") (pintype "bidirectional"))
      (node (ref "U1") (pin "9") (pinfunction "RFN_9") (pintype "bidirectional"))
    )
    (net (code "19") (name "Net-(BATT1-P)") (class "Default")
      (node (ref "BATT1") (pin "+") (pinfunction "P_+") (pintype "bidirectional"))
      (node (ref "J4") (pin "1") (pinfunction "1_1") (pintype "passive"))
    )
    (net (code "20") (name "Net-(C5-Pad1)") (class "Default")
      (node (ref "C5") (pin "1") (pinfunction "1_1") (pintype "passive"))
      (node (ref "U1") (pin "21") (pinfunction "DVDD_21") (pintype "bidirectional"))
      (node (ref "U1") (pin "22") (pinfunction "DVDD_22") (pintype "bidirectional"))
    )
    (net (code "21") (name "Net-(D1-PadA)") (class "Default")
      (node (ref "D1") (pin "A") (pinfunction "A_A") (pintype "passive"))
      (node (ref "R8") (pin "1") (pinfunction "1_1") (pintype "passive"))
    )
    (net (code "22") (name "Net-(D2-PadA)") (class "Default")
      (node (ref "D2") (pin "A") (pinfunction "A_A") (pintype "passive"))
      (node (ref "R7") (pin "1") (pinfunction "1_1") (pintype "passive"))
    )
    (net (code "23") (name "Net-(JP9-1)") (class "Default")
      (node (ref "C3") (pin "1") (pinfunction "1_1") (pintype "passive"))
      (node (ref "JP9") (pin "DTR") (pinfunction "1_DTR") (pintype "passive"))
    )
    (net (code "24") (name "Net-(Q1-D)") (class "Default")
      (node (ref "C12") (pin "2") (pinfunction "2_2") (pintype "passive"))
      (node (ref "D4") (pin "A") (pinfunction "A_A") (pintype "passive"))
      (node (ref "PIN_8") (pin "V-") (pinfunction "V-_V-") (pintype "bidirectional"))
      (node (ref "Q1") (pin "3") (pinfunction "D_3") (pintype "passive"))
    )
    (net (code "25") (name "Net-(Q1-G)") (class "Default")
      (node (ref "Q1") (pin "1") (pinfunction "G_1") (pintype "passive"))
      (node (ref "R12") (pin "2") (pinfunction "2_2") (pintype "passive"))
      (node (ref "R9") (pin "2") (pinfunction "2_2") (pintype "passive"))
    )
    (net (code "26") (name "Net-(Q2-D)") (class "Default")
      (node (ref "C36") (pin "2") (pinfunction "2_2") (pintype "passive"))
      (node (ref "D7") (pin "A") (pinfunction "A_A") (pintype "passive"))
      (node (ref "PIN_5") (pin "V-") (pinfunction "V-_V-") (pintype "bidirectional"))
      (node (ref "Q2") (pin "3") (pinfunction "D_3") (pintype "passive"))
    )
    (net (code "27") (name "Net-(Q2-G)") (class "Default")
      (node (ref "Q2") (pin "1") (pinfunction "G_1") (pintype "passive"))
      (node (ref "R2") (pin "2") (pinfunction "2_2") (pintype "passive"))
      (node (ref "R3") (pin "2") (pinfunction "2_2") (pintype "passive"))
    )
    (net (code "28") (name "Net-(Q3-D)") (class "Default")
      (node (ref "C13") (pin "2") (pinfunction "2_2") (pintype "passive"))
      (node (ref "D5") (pin "A") (pinfunction "A_A") (pintype "passive"))
      (node (ref "PIN_3") (pin "V-") (pinfunction "V-_V-") (pintype "bidirectional"))
      (node (ref "Q3") (pin "3") (pinfunction "D_3") (pintype "passive"))
    )
    (net (code "29") (name "Net-(Q3-G)") (class "Default")
      (node (ref "Q3") (pin "1") (pinfunction "G_1") (pintype "passive"))
      (node (ref "R10") (pin "2") (pinfunction "2_2") (pintype "passive"))
      (node (ref "R13") (pin "2") (pinfunction "2_2") (pintype "passive"))
    )
    (net (code "30") (name "Net-(Q4-D)") (class "Default")
      (node (ref "C35") (pin "2") (pinfunction "2_2") (pintype "passive"))
      (node (ref "D3") (pin "A") (pinfunction "A_A") (pintype "passive"))
      (node (ref "PIN_4") (pin "V-") (pinfunction "V-_V-") (pintype "bidirectional"))
      (node (ref "Q4") (pin "3") (pinfunction "D_3") (pintype "passive"))
    )
    (net (code "31") (name "Net-(Q4-G)") (class "Default")
      (node (ref "Q4") (pin "1") (pinfunction "G_1") (pintype "passive"))
      (node (ref "R11") (pin "2") (pinfunction "2_2") (pintype "passive"))
      (node (ref "R4") (pin "2") (pinfunction "2_2") (pintype "passive"))
    )
    (net (code "32") (name "Net-(U$1-P$7_C1_XM)") (class "Default")
      (node (ref "C21") (pin "2") (pinfunction "2_2") (pintype "passive"))
      (node (ref "U$1") (pin "P$7") (pinfunction "P$7_C1_XM_P$7") (pintype "bidirectional"))
    )
    (net (code "33") (name "Net-(U$1-P$8_SET_XM)") (class "Default")
      (node (ref "C22") (pin "1") (pinfunction "1_1") (pintype "passive"))
      (node (ref "U$1") (pin "P$8") (pinfunction "P$8_SET_XM_P$8") (pintype "bidirectional"))
    )
    (net (code "34") (name "Net-(U$1-P$9_SETP_XM)") (class "Default")
      (node (ref "C22") (pin "2") (pinfunction "2_2") (pintype "passive"))
      (node (ref "U$1") (pin "P$9") (pinfunction "P$9_SETP_XM_P$9") (pintype "bidirectional"))
    )
    (net (code "35") (name "Net-(U$1-P$19_CS_G)") (class "Default")
      (node (ref "R1") (pin "2") (pinfunction "2_2") (pintype "passive"))
      (node (ref "U$1") (pin "P$19") (pinfunction "P$19_CS_G_P$19") (pintype "bidirectional"))
    )
    (net (code "36") (name "Net-(U$1-P$20_CS_XM)") (class "Default")
      (node (ref "R6") (pin "2") (pinfunction "2_2") (pintype "passive"))
      (node (ref "U$1") (pin "P$20") (pinfunction "P$20_CS_XM_P$20") (pintype "bidirectional"))
    )
    (net (code "37") (name "Net-(U$2-NC{slash}FB)") (class "Default")
      (node (ref "C18") (pin "1") (pinfunction "1_1") (pintype "passive"))
      (node (ref "U$2") (pin "4") (pinfunction "NC/FB_4") (pintype "passive"))
    )
    (net (code "38") (name "Net-(U1-AVDD)") (class "Default")
      (node (ref "C6") (pin "1") (pinfunction "1_1") (pintype "passive"))
      (node (ref "U1") (pin "60") (pinfunction "AVDD_60") (pintype "bidirectional"))
    )
    (net (code "39") (name "Net-(U1-XTAL1)") (class "Default")
      (node (ref "C15") (pin "1") (pinfunction "1_1") (pintype "passive"))
      (node (ref "U1") (pin "57") (pinfunction "XTAL1_57") (pintype "bidirectional"))
      (node (ref "Y2") (pin "3") (pinfunction "2_3") (pintype "passive"))
    )
    (net (code "40") (name "Net-(U1-XTAL2)") (class "Default")
      (node (ref "C4") (pin "1") (pinfunction "1_1") (pintype "passive"))
      (node (ref "U1") (pin "56") (pinfunction "XTAL2_56") (pintype "bidirectional"))
      (node (ref "Y2") (pin "1") (pinfunction "1_1") (pintype "passive"))
    )
    (net (code "41") (name "PB4") (class "Default")
      (node (ref "U1") (pin "40") (pinfunction "PB4(OC2A/PCINT4)_40") (pintype "bidirectional"))
    )
    (net (code "42") (name "PB5") (class "Default")
      (node (ref "C23") (pin "1") (pinfunction "1_1") (pintype "passive"))
      (node (ref "R9") (pin "1") (pinfunction "1_1") (pintype "passive"))
      (node (ref "U1") (pin "41") (pinfunction "PB5(OC1A/PCINT5)_41") (pintype "bidirectional"))
    )
    (net (code "43") (name "PB6") (class "Default")
      (node (ref "R7") (pin "2") (pinfunction "2_2") (pintype "passive"))
      (node (ref "U1") (pin "42") (pinfunction "PB6(OC1B/PCINT6)_42") (pintype "bidirectional"))
    )
    (net (code "44") (name "PB7") (class "Default")
      (node (ref "R8") (pin "2") (pinfunction "2_2") (pintype "passive"))
      (node (ref "U1") (pin "43") (pinfunction "PB7(OC0A/OC1C/PCINT7)_43") (pintype "bidirectional"))
    )
    (net (code "45") (name "PD4") (class "Default")
      (node (ref "U1") (pin "29") (pinfunction "PD4(ICP1)_29") (pintype "bidirectional"))
    )
    (net (code "46") (name "PD5") (class "Default")
      (node (ref "U1") (pin "30") (pinfunction "PD5(XCK1)_30") (pintype "bidirectional"))
    )
    (net (code "47") (name "PD6") (class "Default")
      (node (ref "U1") (pin "31") (pinfunction "PD6(T1)_31") (pintype "bidirectional"))
    )
    (net (code "48") (name "PD7") (class "Default")
      (node (ref "U1") (pin "32") (pinfunction "PD7(T0)_32") (pintype "bidirectional"))
    )
    (net (code "49") (name "PE2") (class "Default")
      (node (ref "U1") (pin "48") (pinfunction "PE2(XCK0/AIN0)_48") (pintype "bidirectional"))
    )
    (net (code "50") (name "PE3") (class "Default")
      (node (ref "C28") (pin "1") (pinfunction "1_1") (pintype "passive"))
      (node (ref "R10") (pin "1") (pinfunction "1_1") (pintype "passive"))
      (node (ref "U1") (pin "49") (pinfunction "PE3(OC3A/AIN1)_49") (pintype "bidirectional"))
    )
    (net (code "51") (name "PE4") (class "Default")
      (node (ref "C26") (pin "1") (pinfunction "1_1") (pintype "passive"))
      (node (ref "R4") (pin "1") (pinfunction "1_1") (pintype "passive"))
      (node (ref "U1") (pin "50") (pinfunction "PE4(OC3B/INT4)_50") (pintype "bidirectional"))
    )
    (net (code "52") (name "PE5") (class "Default")
      (node (ref "C25") (pin "1") (pinfunction "1_1") (pintype "passive"))
      (node (ref "R3") (pin "1") (pinfunction "1_1") (pintype "passive"))
      (node (ref "U1") (pin "51") (pinfunction "PE5(OC3C/INT5)_51") (pintype "bidirectional"))
    )
    (net (code "53") (name "PE6") (class "Default")
      (node (ref "U1") (pin "52") (pinfunction "PE6(T3/INT6)_52") (pintype "bidirectional"))
    )
    (net (code "54") (name "PE7") (class "Default")
      (node (ref "U1") (pin "53") (pinfunction "PE7(ICP3/INT7/CLKO)_53") (pintype "bidirectional"))
    )
    (net (code "55") (name "PG0") (class "Default")
      (node (ref "U1") (pin "14") (pinfunction "PG0(DIG3)_14") (pintype "bidirectional"))
    )
    (net (code "56") (name "PG1") (class "Default")
      (node (ref "U1") (pin "15") (pinfunction "PG1(DIG1)_15") (pintype "bidirectional"))
    )
    (net (code "57") (name "PG2") (class "Default")
      (node (ref "U1") (pin "16") (pinfunction "PG2(AMR)_16") (pintype "bidirectional"))
    )
    (net (code "58") (name "PG5") (class "Default")
      (node (ref "U1") (pin "19") (pinfunction "PG5(OC0B)_19") (pintype "bidirectional"))
    )
    (net (code "59") (name "RESET") (class "Default")
      (node (ref "C3") (pin "2") (pinfunction "2_2") (pintype "passive"))
      (node (ref "J1") (pin "5") (pinfunction "5_5") (pintype "passive"))
      (node (ref "R5") (pin "1") (pinfunction "1_1") (pintype "passive"))
      (node (ref "U1") (pin "12") (pinfunction "RSTN_12") (pintype "bidirectional"))
    )
    (net (code "60") (name "RSTON") (class "Default")
      (node (ref "U1") (pin "13") (pinfunction "RSTON_13") (pintype "bidirectional"))
    )
    (net (code "61") (name "RX0") (class "Default")
      (node (ref "JP9") (pin "TXO") (pinfunction "3_TXO") (pintype "passive"))
      (node (ref "U1") (pin "46") (pinfunction "PE0(RXD0/PCINT8)_46") (pintype "bidirectional"))
    )
    (net (code "62") (name "RX1") (class "Default")
      (node (ref "JP1") (pin "RXI") (pinfunction "2_RXI") (pintype "passive"))
      (node (ref "U1") (pin "27") (pinfunction "PD2(RXD1/INT2)_27") (pintype "bidirectional"))
    )
    (net (code "63") (name "SCK") (class "Default")
      (node (ref "J1") (pin "3") (pinfunction "3_3") (pintype "passive"))
      (node (ref "U1") (pin "37") (pinfunction "PB1(SCK/PCINT1)_37") (pintype "bidirectional"))
    )
    (net (code "64") (name "SCL") (class "Default")
      (node (ref "U$1") (pin "P$21") (pinfunction "P$21_SCL/SPC_P$21") (pintype "bidirectional"))
      (node (ref "U1") (pin "25") (pinfunction "PD0(SCL/INT0)_25") (pintype "bidirectional"))
    )
    (net (code "65") (name "SDA") (class "Default")
      (node (ref "U$1") (pin "P$24") (pinfunction "P$24_SDA_P$24") (pintype "bidirectional"))
      (node (ref "U1") (pin "26") (pinfunction "PD1(SDA/INT1)_26") (pintype "bidirectional"))
    )
    (net (code "66") (name "SSN") (class "Default")
      (node (ref "U1") (pin "36") (pinfunction "PB0(SSN/PCINT0)_36") (pintype "bidirectional"))
    )
    (net (code "67") (name "TX0") (class "Default")
      (node (ref "JP9") (pin "RXI") (pinfunction "2_RXI") (pintype "passive"))
      (node (ref "U1") (pin "47") (pinfunction "PE1(TXD0)_47") (pintype "bidirectional"))
    )
    (net (code "68") (name "TX1") (class "Default")
      (node (ref "JP1") (pin "TXO") (pinfunction "3_TXO") (pintype "passive"))
      (node (ref "U1") (pin "28") (pinfunction "PD3(TXD1/INT3)_28") (pintype "bidirectional"))
    )
    (net (code "69") (name "VCC") (class "Default")
      (node (ref "C1") (pin "1") (pinfunction "1_1") (pintype "passive"))
      (node (ref "C12") (pin "1") (pinfunction "1_1") (pintype "passive"))
      (node (ref "C13") (pin "1") (pinfunction "1_1") (pintype "passive"))
      (node (ref "C17") (pin "1") (pinfunction "1_1") (pintype "passive"))
      (node (ref "C35") (pin "1") (pinfunction "1_1") (pintype "passive"))
      (node (ref "C36") (pin "1") (pinfunction "1_1") (pintype "passive"))
      (node (ref "D3") (pin "C") (pinfunction "C_C") (pintype "passive"))
      (node (ref "D4") (pin "C") (pinfunction "C_C") (pintype "passive"))
      (node (ref "D5") (pin "C") (pinfunction "C_C") (pintype "passive"))
      (node (ref "D7") (pin "C") (pinfunction "C_C") (pintype "passive"))
      (node (ref "J4") (pin "2") (pinfunction "2_2") (pintype "passive"))
      (node (ref "PIN_3") (pin "V+") (pinfunction "V+_V+") (pintype "bidirectional"))
      (node (ref "PIN_4") (pin "V+") (pinfunction "V+_V+") (pintype "bidirectional"))
      (node (ref "PIN_5") (pin "V+") (pinfunction "V+_V+") (pintype "bidirectional"))
      (node (ref "PIN_8") (pin "V+") (pinfunction "V+_V+") (pintype "bidirectional"))
      (node (ref "U$2") (pin "1") (pinfunction "IN_1") (pintype "input"))
      (node (ref "U$2") (pin "3") (pinfunction "EN_3") (pintype "input"))
      (node (ref "U$4") (pin "P$1") (pinfunction "1_P$1") (pintype "passive"))
      (node (ref "U$5") (pin "P$1") (pinfunction "1_P$1") (pintype "passive"))
      (node (ref "U$6") (pin "P$1") (pinfunction "1_P$1") (pintype "passive"))
      (node (ref "U$7") (pin "P$1") (pinfunction "1_P$1") (pintype "passive"))
    )
    (net (code "70") (name "unconnected-(C10-Pad1)") (class "Default")
      (node (ref "C10") (pin "1") (pinfunction "1_1") (pintype "passive"))
    )
    (net (code "71") (name "unconnected-(C10-Pad2)") (class "Default")
      (node (ref "C10") (pin "2") (pinfunction "2_2") (pintype "passive"))
    )
    (net (code "72") (name "unconnected-(C14-Pad1)") (class "Default")
      (node (ref "C14") (pin "1") (pinfunction "1_1") (pintype "passive"))
    )
    (net (code "73") (name "unconnected-(C14-Pad2)") (class "Default")
      (node (ref "C14") (pin "2") (pinfunction "2_2") (pintype "passive"))
    )
    (net (code "74") (name "unconnected-(J1-Pad2)") (class "Default")
      (node (ref "J1") (pin "2") (pinfunction "2_2") (pintype "passive"))
    )
    (net (code "75") (name "unconnected-(JP1-1-PadDTR)") (class "Default")
      (node (ref "JP1") (pin "DTR") (pinfunction "1_DTR") (pintype "passive"))
    )
    (net (code "76") (name "unconnected-(JP1-4-PadVCC)") (class "Default")
      (node (ref "JP1") (pin "VCC") (pinfunction "4_VCC") (pintype "passive"))
    )
    (net (code "77") (name "unconnected-(JP1-5-PadCTS)") (class "Default")
      (node (ref "JP1") (pin "CTS") (pinfunction "5_CTS") (pintype "passive"))
    )
    (net (code "78") (name "unconnected-(JP9-4-PadVCC)") (class "Default")
      (node (ref "JP9") (pin "VCC") (pinfunction "4_VCC") (pintype "passive"))
    )
    (net (code "79") (name "unconnected-(JP9-5-PadCTS)") (class "Default")
      (node (ref "JP9") (pin "CTS") (pinfunction "5_CTS") (pintype "passive"))
    )
    (net (code "80") (name "unconnected-(U$1-P$1_RES-PadP$1)") (class "Default")
      (node (ref "U$1") (pin "P$1") (pinfunction "P$1_RES_P$1") (pintype "bidirectional"))
    )
    (net (code "81") (name "unconnected-(U$1-P$10_DEN_G-PadP$10)") (class "Default")
      (node (ref "U$1") (pin "P$10") (pinfunction "P$10_DEN_G_P$10") (pintype "bidirectional"))
    )
    (net (code "82") (name "unconnected-(U$1-P$11_INT_G-PadP$11)") (class "Default")
      (node (ref "U$1") (pin "P$11") (pinfunction "P$11_INT_G_P$11") (pintype "bidirectional"))
    )
    (net (code "83") (name "unconnected-(U$1-P$12_DADY_G-PadP$12)") (class "Default")
      (node (ref "U$1") (pin "P$12") (pinfunction "P$12_DADY_G_P$12") (pintype "bidirectional"))
    )
    (net (code "84") (name "unconnected-(U$1-P$13_INT1_XM-PadP$13)") (class "Default")
      (node (ref "U$1") (pin "P$13") (pinfunction "P$13_INT1_XM_P$13") (pintype "bidirectional"))
    )
    (net (code "85") (name "unconnected-(U$1-P$14_INT2_XM-PadP$14)") (class "Default")
      (node (ref "U$1") (pin "P$14") (pinfunction "P$14_INT2_XM_P$14") (pintype "bidirectional"))
    )
    (net (code "86") (name "unconnected-(U1-PG3(TOSC2)-Pad17)") (class "Default")
      (node (ref "U1") (pin "17") (pinfunction "PG3(TOSC2)_17") (pintype "bidirectional"))
    )
    (net (code "87") (name "unconnected-(U1-PG4(TOSC1)-Pad18)") (class "Default")
      (node (ref "U1") (pin "18") (pinfunction "PG4(TOSC1)_18") (pintype "bidirectional"))
    )
  )
)
